# stmbluepill.net
KiCad netlist of a schematic drawn in EAGLE
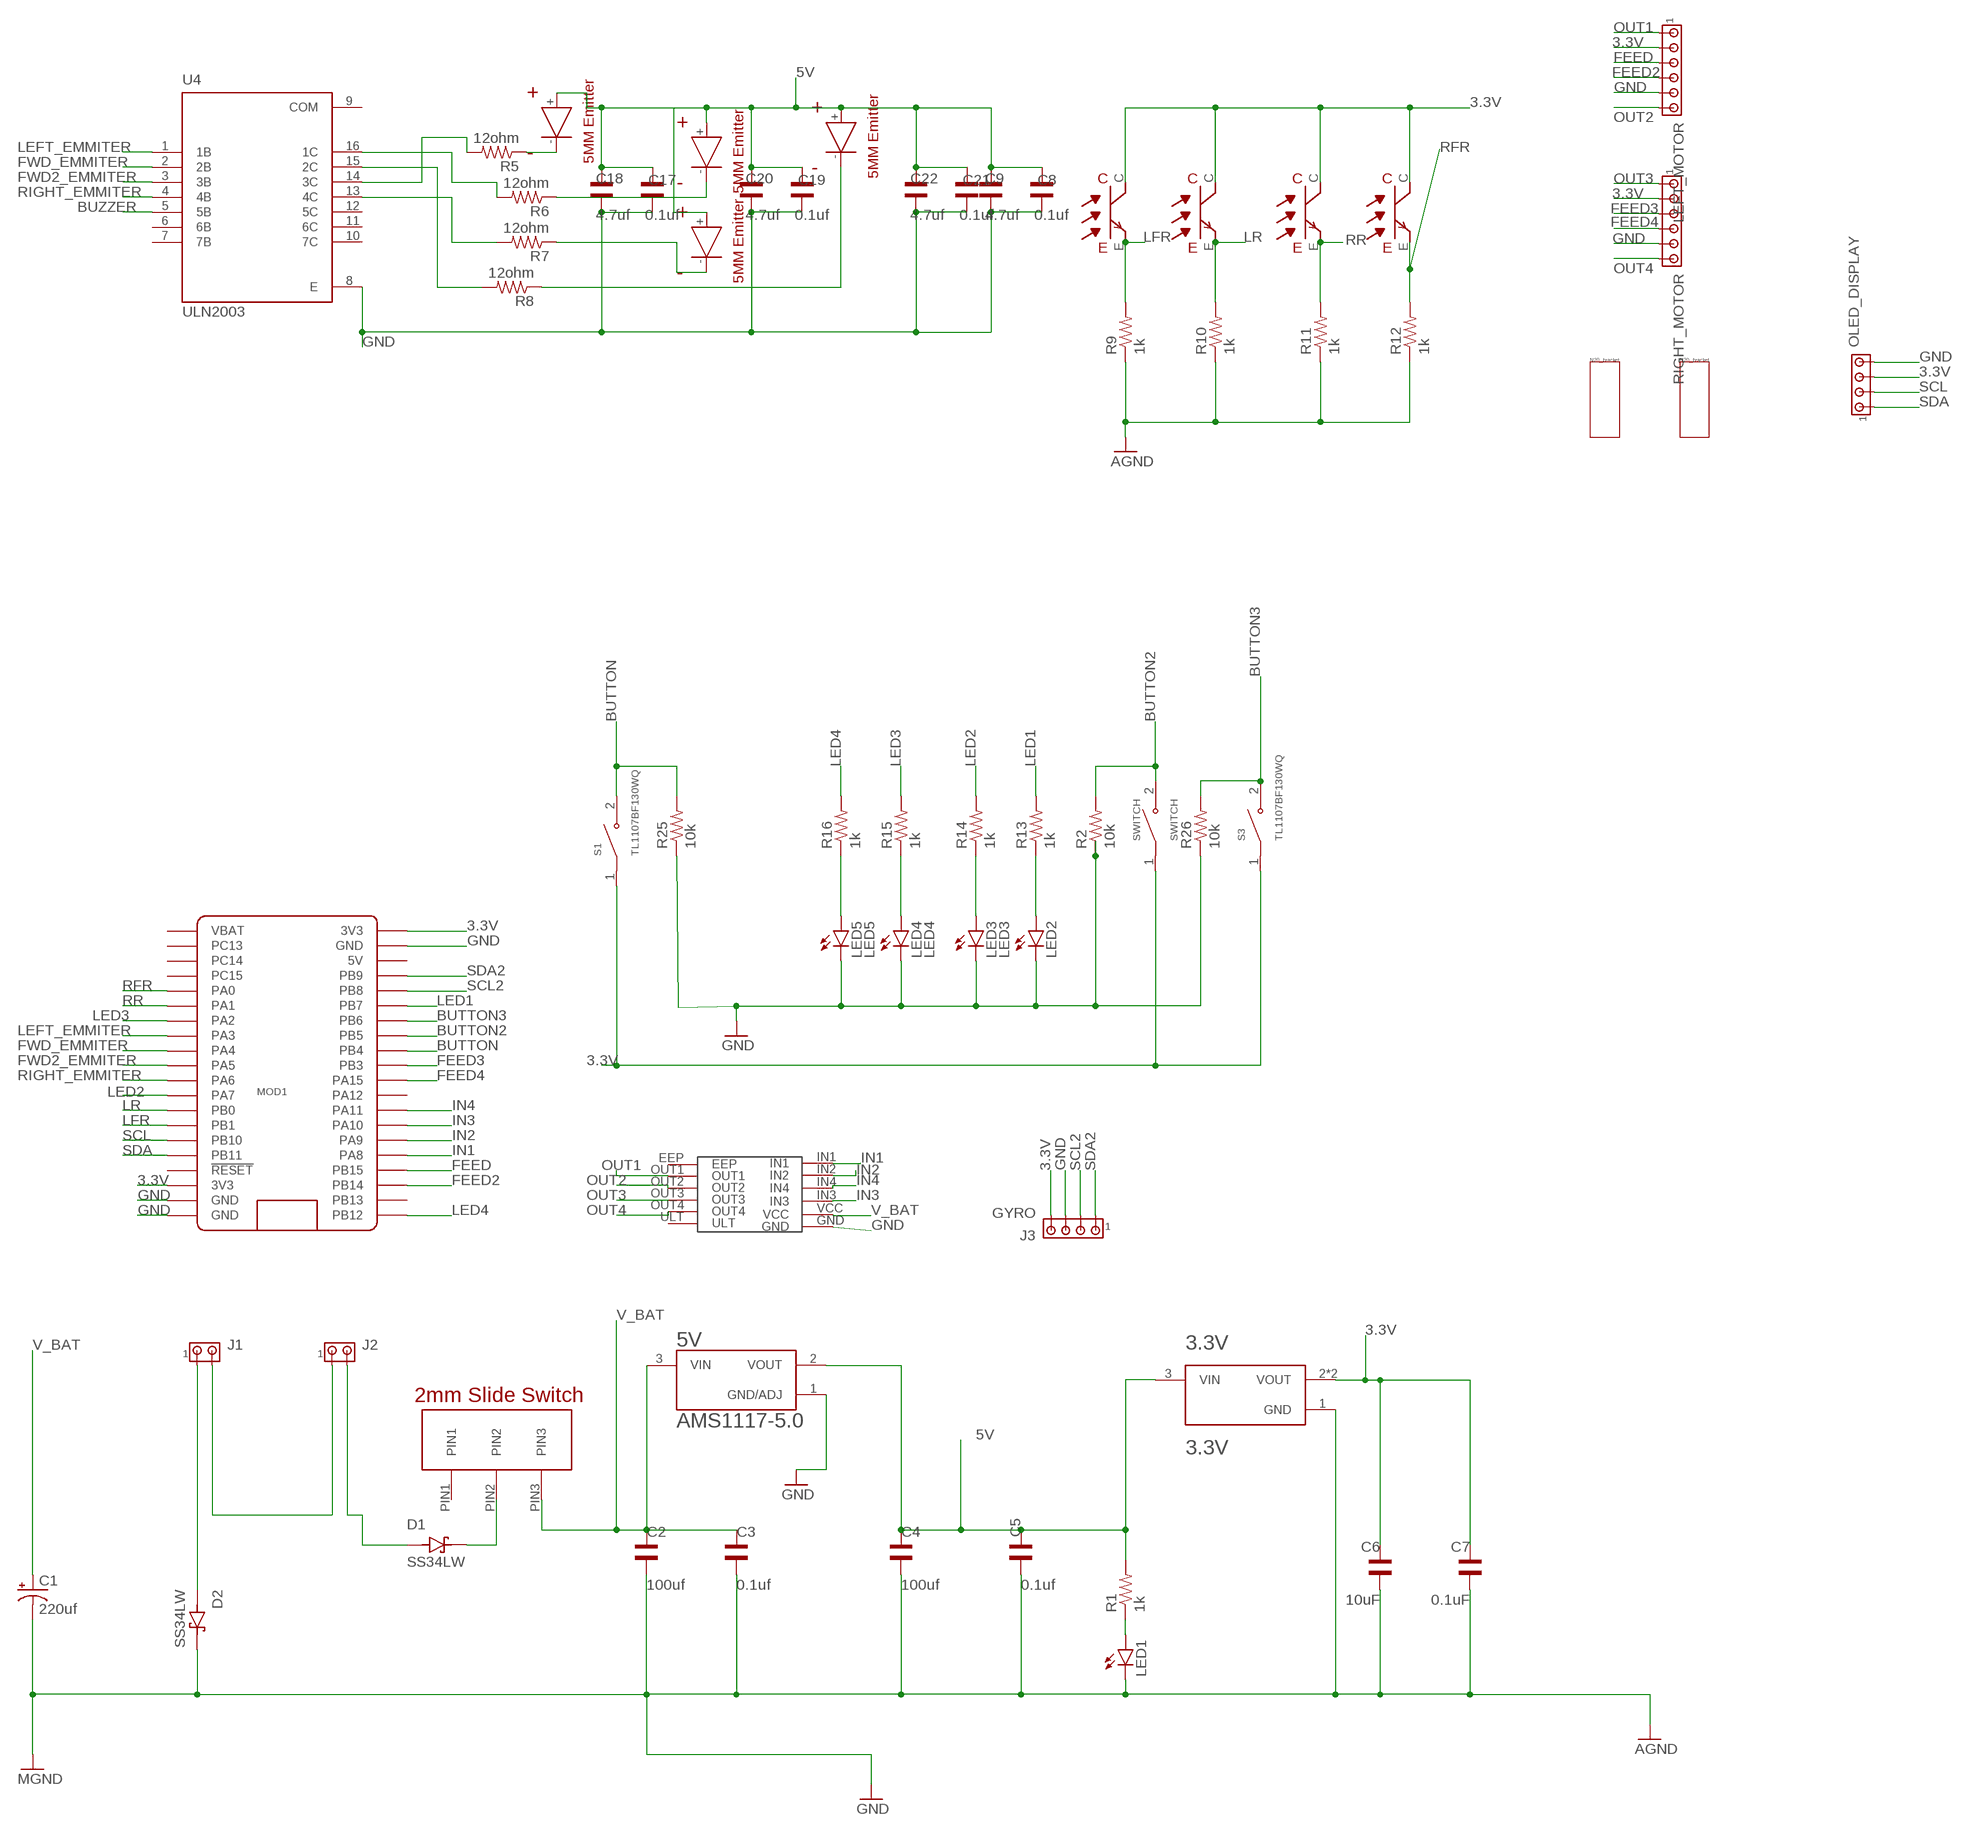
[diagram p0: schematic, sheet 1]

(export (version "E")
  (design (tool "Eeschema 10.0.6"))
  (components
    (comp (ref "3.3V")
      (value "3.3V")
      (footprint "eagle-import:SOT230P700X180-4N")
      (fields (field (name "MF") "STMicroelectronics") (field (name "MP") "LDL1117S33R"))
      (libsource (lib "eagle-import") (part "LDL1117S33R"))
    )
    (comp (ref "5V")
      (value "AMS1117-5.0")
      (footprint "eagle-import:SOT229P700X180-4N")
      (fields (field (name "MF") "Advanced Monolithic Systems"))
      (libsource (lib "eagle-import") (part "AMS1117-5.0"))
    )
    (comp (ref "C1")
      (value "220uf")
      (footprint "eagle-import:EIA3216")
      (libsource (lib "eagle-import") (part "CAP_POL1206"))
    )
    (comp (ref "C2")
      (value "100uf")
      (footprint "eagle-import:WCAP-CSGP_885012206026")
      (fields (field (name "MF") "Würth Elektronik") (field (name "MP") "885012206026"))
      (libsource (lib "eagle-import") (part "885012206026"))
    )
    (comp (ref "C3")
      (value "0.1uf")
      (footprint "eagle-import:WCAP-CSGP_885012206026")
      (fields (field (name "MF") "Würth Elektronik") (field (name "MP") "885012206026"))
      (libsource (lib "eagle-import") (part "885012206026"))
    )
    (comp (ref "C4")
      (value "100uf")
      (footprint "eagle-import:WCAP-CSGP_885012206026")
      (fields (field (name "MF") "Würth Elektronik") (field (name "MP") "885012206026"))
      (libsource (lib "eagle-import") (part "885012206026"))
    )
    (comp (ref "C5")
      (value "0.1uf")
      (footprint "eagle-import:WCAP-CSGP_885012206026")
      (fields (field (name "MF") "Würth Elektronik") (field (name "MP") "885012206026"))
      (libsource (lib "eagle-import") (part "885012206026"))
    )
    (comp (ref "C6")
      (value "10uF")
      (footprint "eagle-import:WCAP-CSGP_885012206026")
      (fields (field (name "MF") "Würth Elektronik") (field (name "MP") "885012206026"))
      (libsource (lib "eagle-import") (part "885012206026"))
    )
    (comp (ref "C7")
      (value "0.1uF")
      (footprint "eagle-import:WCAP-CSGP_885012206026")
      (fields (field (name "MF") "Würth Elektronik") (field (name "MP") "885012206026"))
      (libsource (lib "eagle-import") (part "885012206026"))
    )
    (comp (ref "C8")
      (value "0.1uf")
      (footprint "eagle-import:WCAP-CSGP_885012206026")
      (fields (field (name "MF") "Würth Elektronik") (field (name "MP") "885012206026"))
      (libsource (lib "eagle-import") (part "885012206026"))
    )
    (comp (ref "C9")
      (value "4.7uf")
      (footprint "eagle-import:WCAP-CSGP_885012206026")
      (fields (field (name "MF") "Würth Elektronik") (field (name "MP") "885012206026"))
      (libsource (lib "eagle-import") (part "885012206026"))
    )
    (comp (ref "C17")
      (value "0.1uf")
      (footprint "eagle-import:WCAP-CSGP_885012206026")
      (fields (field (name "MF") "Würth Elektronik") (field (name "MP") "885012206026"))
      (libsource (lib "eagle-import") (part "885012206026"))
    )
    (comp (ref "C18")
      (value "4.7uf")
      (footprint "eagle-import:WCAP-CSGP_885012206026")
      (fields (field (name "MF") "Würth Elektronik") (field (name "MP") "885012206026"))
      (libsource (lib "eagle-import") (part "885012206026"))
    )
    (comp (ref "C19")
      (value "0.1uf")
      (footprint "eagle-import:WCAP-CSGP_885012206026")
      (fields (field (name "MF") "Würth Elektronik") (field (name "MP") "885012206026"))
      (libsource (lib "eagle-import") (part "885012206026"))
    )
    (comp (ref "C20")
      (value "4.7uf")
      (footprint "eagle-import:WCAP-CSGP_885012206026")
      (fields (field (name "MF") "Würth Elektronik") (field (name "MP") "885012206026"))
      (libsource (lib "eagle-import") (part "885012206026"))
    )
    (comp (ref "C21")
      (value "0.1uf")
      (footprint "eagle-import:WCAP-CSGP_885012206026")
      (fields (field (name "MF") "Würth Elektronik") (field (name "MP") "885012206026"))
      (libsource (lib "eagle-import") (part "885012206026"))
    )
    (comp (ref "C22")
      (value "4.7uf")
      (footprint "eagle-import:WCAP-CSGP_885012206026")
      (fields (field (name "MF") "Würth Elektronik") (field (name "MP") "885012206026"))
      (libsource (lib "eagle-import") (part "885012206026"))
    )
    (comp (ref "D1")
      (value "SS34LW")
      (footprint "eagle-import:SODFL3718X102N")
      (fields (field (name "MF") "Taiwan Semiconductor"))
      (libsource (lib "eagle-import") (part "SS34LW"))
    )
    (comp (ref "D2")
      (value "SS34LW")
      (footprint "eagle-import:SODFL3718X102N")
      (fields (field (name "MF") "Taiwan Semiconductor"))
      (libsource (lib "eagle-import") (part "SS34LW"))
    )
    (comp (ref "EMMI1")
      (value "EMITTER")
      (footprint "eagle-import:EMITTER")
      (libsource (lib "eagle-import") (part "EMITTER"))
    )
    (comp (ref "J1")
      (value "MTA02-100")
      (footprint "eagle-import:10X02MTA")
      (libsource (lib "eagle-import") (part "MTA02-100"))
    )
    (comp (ref "J2")
      (value "MTA02-100")
      (footprint "eagle-import:10X02MTA")
      (libsource (lib "eagle-import") (part "MTA02-100"))
    )
    (comp (ref "J3")
      (value "GYRO")
      (footprint "eagle-import:10X04MTA")
      (libsource (lib "eagle-import") (part "MTA04-100"))
    )
    (comp (ref "LED1")
      (value "LEDCHIPLED_0805")
      (footprint "eagle-import:CHIPLED_0805")
      (libsource (lib "eagle-import") (part "LEDCHIPLED_0805"))
    )
    (comp (ref "LED2")
      (value "LEDCHIPLED_0805")
      (footprint "eagle-import:CHIPLED_0805")
      (libsource (lib "eagle-import") (part "LEDCHIPLED_0805"))
    )
    (comp (ref "LED3")
      (value "LED3")
      (footprint "eagle-import:CHIPLED_0805")
      (libsource (lib "eagle-import") (part "LEDCHIPLED_0805"))
    )
    (comp (ref "LED4")
      (value "LED4")
      (footprint "eagle-import:CHIPLED_0805")
      (libsource (lib "eagle-import") (part "LEDCHIPLED_0805"))
    )
    (comp (ref "LED5")
      (value "LED5")
      (footprint "eagle-import:CHIPLED_0805")
      (libsource (lib "eagle-import") (part "LEDCHIPLED_0805"))
    )
    (comp (ref "LEFT_MOTOR")
      (value "MTA06-100")
      (footprint "eagle-import:10X06MTA")
      (libsource (lib "eagle-import") (part "MTA06-100"))
    )
    (comp (ref "MOD1")
      (value "BLUE_PILLADVANCED")
      (footprint "eagle-import:BLUE_PILL_ADV")
      (libsource (lib "eagle-import") (part "BLUE_PILLADVANCED"))
    )
    (comp (ref "OLED_DISPLAY")
      (value "MTA04-100")
      (footprint "eagle-import:10X04MTA")
      (libsource (lib "eagle-import") (part "MTA04-100"))
    )
    (comp (ref "R1")
      (value "1k")
      (footprint "eagle-import:0603-RES")
      (libsource (lib "eagle-import") (part "RESISTOR0603-RES"))
    )
    (comp (ref "R2")
      (value "10k")
      (footprint "eagle-import:0603-RES")
      (libsource (lib "eagle-import") (part "RESISTOR0603-RES"))
    )
    (comp (ref "R5")
      (value "12ohm")
      (footprint "eagle-import:0603-RES")
      (libsource (lib "eagle-import") (part "RESISTOR0603-RES"))
    )
    (comp (ref "R6")
      (value "12ohm")
      (footprint "eagle-import:0603-RES")
      (libsource (lib "eagle-import") (part "RESISTOR0603-RES"))
    )
    (comp (ref "R7")
      (value "12ohm")
      (footprint "eagle-import:0603-RES")
      (libsource (lib "eagle-import") (part "RESISTOR0603-RES"))
    )
    (comp (ref "R8")
      (value "12ohm")
      (footprint "eagle-import:0603-RES")
      (libsource (lib "eagle-import") (part "RESISTOR0603-RES"))
    )
    (comp (ref "R9")
      (value "1k")
      (footprint "eagle-import:0603-RES")
      (libsource (lib "eagle-import") (part "RESISTOR0603-RES"))
    )
    (comp (ref "R10")
      (value "1k")
      (footprint "eagle-import:0603-RES")
      (libsource (lib "eagle-import") (part "RESISTOR0603-RES"))
    )
    (comp (ref "R11")
      (value "1k")
      (footprint "eagle-import:0603-RES")
      (libsource (lib "eagle-import") (part "RESISTOR0603-RES"))
    )
    (comp (ref "R12")
      (value "1k")
      (footprint "eagle-import:0603-RES")
      (libsource (lib "eagle-import") (part "RESISTOR0603-RES"))
    )
    (comp (ref "R13")
      (value "1k")
      (footprint "eagle-import:0603-RES")
      (libsource (lib "eagle-import") (part "RESISTOR0603-RES"))
    )
    (comp (ref "R14")
      (value "1k")
      (footprint "eagle-import:0603-RES")
      (libsource (lib "eagle-import") (part "RESISTOR0603-RES"))
    )
    (comp (ref "R15")
      (value "1k")
      (footprint "eagle-import:0603-RES")
      (libsource (lib "eagle-import") (part "RESISTOR0603-RES"))
    )
    (comp (ref "R16")
      (value "1k")
      (footprint "eagle-import:0603-RES")
      (libsource (lib "eagle-import") (part "RESISTOR0603-RES"))
    )
    (comp (ref "R25")
      (value "10k")
      (footprint "eagle-import:0603-RES")
      (libsource (lib "eagle-import") (part "RESISTOR0603-RES"))
    )
    (comp (ref "R26")
      (value "10k")
      (footprint "eagle-import:0603-RES")
      (libsource (lib "eagle-import") (part "RESISTOR0603-RES"))
    )
    (comp (ref "RIGHT_MOTOR")
      (value "MTA06-100")
      (footprint "eagle-import:10X06MTA")
      (libsource (lib "eagle-import") (part "MTA06-100"))
    )
    (comp (ref "S1")
      (value "TL1107BF130WQ")
      (footprint "eagle-import:SW_TL1107BF130WQ")
      (fields (field (name "MF") "E-Switch"))
      (libsource (lib "eagle-import") (part "TL1107BF130WQ"))
    )
    (comp (ref "S3")
      (value "TL1107BF130WQ")
      (footprint "eagle-import:SW_TL1107BF130WQ")
      (fields (field (name "MF") "E-Switch"))
      (libsource (lib "eagle-import") (part "TL1107BF130WQ"))
    )
    (comp (ref "SWITCH")
      (value "SWITCH")
      (footprint "eagle-import:SW_TL1107BF130WQ")
      (fields (field (name "MF") "E-Switch") (field (name "MP") "TL1107BF130WQ"))
      (libsource (lib "eagle-import") (part "TL1107BF130WQ"))
    )
    (comp (ref "U$1")
      (value "N20_BRACKET")
      (footprint "eagle-import:BRACKER")
      (libsource (lib "eagle-import") (part "N20_BRACKET"))
    )
    (comp (ref "U$4")
      (value "N20_BRACKET")
      (footprint "eagle-import:BRACKER")
      (libsource (lib "eagle-import") (part "N20_BRACKET"))
    )
    (comp (ref "U$8")
      (value "2MMS_SLIDE_SWITCH")
      (footprint "eagle-import:2MMS_SLIDE_SWITCH")
      (libsource (lib "eagle-import") (part "2MMS_SLIDE_SWITCH"))
    )
    (comp (ref "U$11")
      (value "DRV8833")
      (footprint "eagle-import:DRV8833")
      (libsource (lib "eagle-import") (part "DRV8833"))
    )
    (comp (ref "U$12")
      (value "RECEIVER")
      (footprint "eagle-import:RECEIVER")
      (libsource (lib "eagle-import") (part "RECEIVER"))
    )
    (comp (ref "U$13")
      (value "EMITTER")
      (footprint "eagle-import:EMITTER")
      (libsource (lib "eagle-import") (part "EMITTER"))
    )
    (comp (ref "U$14")
      (value "EMITTER")
      (footprint "eagle-import:EMITTER")
      (libsource (lib "eagle-import") (part "EMITTER"))
    )
    (comp (ref "U$15")
      (value "EMITTER")
      (footprint "eagle-import:EMITTER")
      (libsource (lib "eagle-import") (part "EMITTER"))
    )
    (comp (ref "U$16")
      (value "RECEIVER")
      (footprint "eagle-import:RECEIVER")
      (libsource (lib "eagle-import") (part "RECEIVER"))
    )
    (comp (ref "U$17")
      (value "RECEIVER")
      (footprint "eagle-import:RECEIVER")
      (libsource (lib "eagle-import") (part "RECEIVER"))
    )
    (comp (ref "U$18")
      (value "RECEIVER")
      (footprint "eagle-import:RECEIVER")
      (libsource (lib "eagle-import") (part "RECEIVER"))
    )
    (comp (ref "U4")
      (value "ULN2003")
      (footprint "eagle-import:SOP65P640X120-16N")
      (fields (field (name "MF") "Texas Instruments") (field (name "MP") "ULN2003APWR"))
      (libsource (lib "eagle-import") (part "ULN2003APWR"))
    )
  )
  (nets
    (net (code "1") (name "/3.3V") (class "Default")
      (node (ref "3.3V") (pin "2") (pinfunction "VOUT_2") (pintype "output"))
      (node (ref "3.3V") (pin "4") (pinfunction "VOUT_4") (pintype "output"))
      (node (ref "C6") (pin "2") (pinfunction "2_2") (pintype "passive"))
      (node (ref "C7") (pin "2") (pinfunction "2_2") (pintype "passive"))
      (node (ref "J3") (pin "4") (pinfunction "4_4") (pintype "passive"))
      (node (ref "LEFT_MOTOR") (pin "2") (pinfunction "2_2") (pintype "passive"))
      (node (ref "MOD1") (pin "P$20") (pinfunction "3V3_P$20") (pintype "bidirectional"))
      (node (ref "MOD1") (pin "P$23") (pinfunction "3V3_P$23") (pintype "bidirectional"))
      (node (ref "OLED_DISPLAY") (pin "3") (pinfunction "3_3") (pintype "passive"))
      (node (ref "RIGHT_MOTOR") (pin "2") (pinfunction "2_2") (pintype "passive"))
      (node (ref "S1") (pin "1") (pinfunction "1_1") (pintype "passive"))
      (node (ref "S3") (pin "1") (pinfunction "1_1") (pintype "passive"))
      (node (ref "SWITCH") (pin "1") (pinfunction "1_1") (pintype "passive"))
      (node (ref "U$12") (pin "C") (pinfunction "C_C") (pintype "bidirectional"))
      (node (ref "U$16") (pin "C") (pinfunction "C_C") (pintype "bidirectional"))
      (node (ref "U$17") (pin "C") (pinfunction "C_C") (pintype "bidirectional"))
      (node (ref "U$18") (pin "C") (pinfunction "C_C") (pintype "bidirectional"))
    )
    (net (code "2") (name "/5V") (class "Default")
      (node (ref "3.3V") (pin "3") (pinfunction "VIN_3") (pintype "input"))
      (node (ref "5V") (pin "2") (pinfunction "VOUT_2") (pintype "output"))
      (node (ref "C17") (pin "2") (pinfunction "2_2") (pintype "passive"))
      (node (ref "C18") (pin "2") (pinfunction "2_2") (pintype "passive"))
      (node (ref "C19") (pin "2") (pinfunction "2_2") (pintype "passive"))
      (node (ref "C20") (pin "2") (pinfunction "2_2") (pintype "passive"))
      (node (ref "C21") (pin "2") (pinfunction "2_2") (pintype "passive"))
      (node (ref "C22") (pin "2") (pinfunction "2_2") (pintype "passive"))
      (node (ref "C4") (pin "2") (pinfunction "2_2") (pintype "passive"))
      (node (ref "C5") (pin "2") (pinfunction "2_2") (pintype "passive"))
      (node (ref "C8") (pin "2") (pinfunction "2_2") (pintype "passive"))
      (node (ref "C9") (pin "2") (pinfunction "2_2") (pintype "passive"))
      (node (ref "EMMI1") (pin "+") (pinfunction "+_+") (pintype "bidirectional"))
      (node (ref "R1") (pin "2") (pinfunction "2_2") (pintype "passive"))
      (node (ref "U$13") (pin "+") (pinfunction "+_+") (pintype "bidirectional"))
      (node (ref "U$14") (pin "+") (pinfunction "+_+") (pintype "bidirectional"))
      (node (ref "U$15") (pin "+") (pinfunction "+_+") (pintype "bidirectional"))
    )
    (net (code "3") (name "/BUTTON") (class "Default")
      (node (ref "MOD1") (pin "P$12") (pinfunction "PB4_P$12") (pintype "bidirectional"))
      (node (ref "R25") (pin "2") (pinfunction "2_2") (pintype "passive"))
      (node (ref "S1") (pin "2") (pinfunction "2_2") (pintype "passive"))
    )
    (net (code "4") (name "/BUTTON2") (class "Default")
      (node (ref "MOD1") (pin "P$13") (pinfunction "PB5_P$13") (pintype "bidirectional"))
      (node (ref "R2") (pin "2") (pinfunction "2_2") (pintype "passive"))
      (node (ref "SWITCH") (pin "2") (pinfunction "2_2") (pintype "passive"))
    )
    (net (code "5") (name "/BUTTON3") (class "Default")
      (node (ref "MOD1") (pin "P$14") (pinfunction "PB6_P$14") (pintype "bidirectional"))
      (node (ref "R26") (pin "2") (pinfunction "2_2") (pintype "passive"))
      (node (ref "S3") (pin "2") (pinfunction "2_2") (pintype "passive"))
    )
    (net (code "6") (name "/BUZZER") (class "Default")
      (node (ref "U4") (pin "5") (pinfunction "5B_5") (pintype "input"))
    )
    (net (code "7") (name "/COM") (class "Default")
      (node (ref "U4") (pin "9") (pinfunction "COM_9") (pintype "power_in"))
    )
    (net (code "8") (name "/FEED") (class "Default")
      (node (ref "LEFT_MOTOR") (pin "3") (pinfunction "3_3") (pintype "passive"))
      (node (ref "MOD1") (pin "P$4") (pinfunction "PB15_P$4") (pintype "bidirectional"))
    )
    (net (code "9") (name "/FEED2") (class "Default")
      (node (ref "LEFT_MOTOR") (pin "4") (pinfunction "4_4") (pintype "passive"))
      (node (ref "MOD1") (pin "P$3") (pinfunction "PB14_P$3") (pintype "bidirectional"))
    )
    (net (code "10") (name "/FEED3") (class "Default")
      (node (ref "MOD1") (pin "P$11") (pinfunction "PB3_P$11") (pintype "bidirectional"))
      (node (ref "RIGHT_MOTOR") (pin "3") (pinfunction "3_3") (pintype "passive"))
    )
    (net (code "11") (name "/FEED4") (class "Default")
      (node (ref "MOD1") (pin "P$10") (pinfunction "PA15_P$10") (pintype "bidirectional"))
      (node (ref "RIGHT_MOTOR") (pin "4") (pinfunction "4_4") (pintype "passive"))
    )
    (net (code "12") (name "/FWD2_EMMITER") (class "Default")
      (node (ref "MOD1") (pin "P$31") (pinfunction "PA5_P$31") (pintype "bidirectional"))
      (node (ref "U4") (pin "3") (pinfunction "3B_3") (pintype "input"))
    )
    (net (code "13") (name "/FWD_EMMITER") (class "Default")
      (node (ref "MOD1") (pin "P$32") (pinfunction "PA4_P$32") (pintype "bidirectional"))
      (node (ref "U4") (pin "2") (pinfunction "2B_2") (pintype "input"))
    )
    (net (code "14") (name "/IN1") (class "Default")
      (node (ref "MOD1") (pin "P$5") (pinfunction "PA8_P$5") (pintype "bidirectional"))
      (node (ref "U$11") (pin "IN1") (pinfunction "IN1_IN1") (pintype "bidirectional"))
    )
    (net (code "15") (name "/IN2") (class "Default")
      (node (ref "MOD1") (pin "P$6") (pinfunction "PA9_P$6") (pintype "bidirectional"))
      (node (ref "U$11") (pin "IN2") (pinfunction "IN2_IN2") (pintype "bidirectional"))
    )
    (net (code "16") (name "/IN3") (class "Default")
      (node (ref "MOD1") (pin "P$7") (pinfunction "PA10_P$7") (pintype "bidirectional"))
      (node (ref "U$11") (pin "IN3") (pinfunction "IN3_IN3") (pintype "bidirectional"))
    )
    (net (code "17") (name "/IN4") (class "Default")
      (node (ref "MOD1") (pin "P$8") (pinfunction "PA11_P$8") (pintype "bidirectional"))
      (node (ref "U$11") (pin "IN4") (pinfunction "IN4_IN4") (pintype "bidirectional"))
    )
    (net (code "18") (name "/LED1") (class "Default")
      (node (ref "MOD1") (pin "P$15") (pinfunction "PB7_P$15") (pintype "bidirectional"))
      (node (ref "R13") (pin "2") (pinfunction "2_2") (pintype "passive"))
    )
    (net (code "19") (name "/LED2") (class "Default")
      (node (ref "MOD1") (pin "P$29") (pinfunction "PA7_P$29") (pintype "bidirectional"))
      (node (ref "R14") (pin "2") (pinfunction "2_2") (pintype "passive"))
    )
    (net (code "20") (name "/LED3") (class "Default")
      (node (ref "MOD1") (pin "P$34") (pinfunction "PA2_P$34") (pintype "bidirectional"))
      (node (ref "R15") (pin "2") (pinfunction "2_2") (pintype "passive"))
    )
    (net (code "21") (name "/LED4") (class "Default")
      (node (ref "MOD1") (pin "P$1") (pinfunction "PB12_P$1") (pintype "bidirectional"))
      (node (ref "R16") (pin "2") (pinfunction "2_2") (pintype "passive"))
    )
    (net (code "22") (name "/LEFT_EMMITER") (class "Default")
      (node (ref "MOD1") (pin "P$33") (pinfunction "PA3_P$33") (pintype "bidirectional"))
      (node (ref "U4") (pin "1") (pinfunction "1B_1") (pintype "input"))
    )
    (net (code "23") (name "/LFR") (class "Default")
      (node (ref "MOD1") (pin "P$27") (pinfunction "PB1_P$27") (pintype "bidirectional"))
      (node (ref "R9") (pin "2") (pinfunction "2_2") (pintype "passive"))
      (node (ref "U$18") (pin "E") (pinfunction "E_E") (pintype "bidirectional"))
    )
    (net (code "24") (name "/LR") (class "Default")
      (node (ref "MOD1") (pin "P$28") (pinfunction "PB0_P$28") (pintype "bidirectional"))
      (node (ref "R10") (pin "2") (pinfunction "2_2") (pintype "passive"))
      (node (ref "U$17") (pin "E") (pinfunction "E_E") (pintype "bidirectional"))
    )
    (net (code "25") (name "/OUT1") (class "Default")
      (node (ref "LEFT_MOTOR") (pin "1") (pinfunction "1_1") (pintype "passive"))
      (node (ref "U$11") (pin "OUT1") (pinfunction "OUT1_OUT1") (pintype "bidirectional"))
    )
    (net (code "26") (name "/OUT2") (class "Default")
      (node (ref "LEFT_MOTOR") (pin "6") (pinfunction "6_6") (pintype "passive"))
      (node (ref "U$11") (pin "OUT2") (pinfunction "OUT2_OUT2") (pintype "bidirectional"))
    )
    (net (code "27") (name "/OUT3") (class "Default")
      (node (ref "RIGHT_MOTOR") (pin "1") (pinfunction "1_1") (pintype "passive"))
      (node (ref "U$11") (pin "OUT3") (pinfunction "OUT3_OUT3") (pintype "bidirectional"))
    )
    (net (code "28") (name "/OUT4") (class "Default")
      (node (ref "RIGHT_MOTOR") (pin "6") (pinfunction "6_6") (pintype "passive"))
      (node (ref "U$11") (pin "OUT4") (pinfunction "OUT4_OUT4") (pintype "bidirectional"))
    )
    (net (code "29") (name "/RFR") (class "Default")
      (node (ref "MOD1") (pin "P$36") (pinfunction "PA0_P$36") (pintype "bidirectional"))
      (node (ref "R12") (pin "2") (pinfunction "2_2") (pintype "passive"))
      (node (ref "U$12") (pin "E") (pinfunction "E_E") (pintype "bidirectional"))
    )
    (net (code "30") (name "/RIGHT_EMMITER") (class "Default")
      (node (ref "MOD1") (pin "P$30") (pinfunction "PA6_P$30") (pintype "bidirectional"))
      (node (ref "U4") (pin "4") (pinfunction "4B_4") (pintype "input"))
    )
    (net (code "31") (name "/RR") (class "Default")
      (node (ref "MOD1") (pin "P$35") (pinfunction "PA1_P$35") (pintype "bidirectional"))
      (node (ref "R11") (pin "2") (pinfunction "2_2") (pintype "passive"))
      (node (ref "U$16") (pin "E") (pinfunction "E_E") (pintype "bidirectional"))
    )
    (net (code "32") (name "/SCL") (class "Default")
      (node (ref "MOD1") (pin "P$26") (pinfunction "PB10_P$26") (pintype "bidirectional"))
      (node (ref "OLED_DISPLAY") (pin "2") (pinfunction "2_2") (pintype "passive"))
    )
    (net (code "33") (name "/SCL2") (class "Default")
      (node (ref "J3") (pin "2") (pinfunction "2_2") (pintype "passive"))
      (node (ref "MOD1") (pin "P$16") (pinfunction "PB8_P$16") (pintype "bidirectional"))
    )
    (net (code "34") (name "/SDA") (class "Default")
      (node (ref "MOD1") (pin "P$25") (pinfunction "PB11_P$25") (pintype "bidirectional"))
      (node (ref "OLED_DISPLAY") (pin "1") (pinfunction "1_1") (pintype "passive"))
    )
    (net (code "35") (name "/SDA2") (class "Default")
      (node (ref "J3") (pin "1") (pinfunction "1_1") (pintype "passive"))
      (node (ref "MOD1") (pin "P$17") (pinfunction "PB9_P$17") (pintype "bidirectional"))
    )
    (net (code "36") (name "/V_BAT") (class "Default")
      (node (ref "5V") (pin "3") (pinfunction "VIN_3") (pintype "input"))
      (node (ref "C1") (pin "A") (pinfunction "+_A") (pintype "passive"))
      (node (ref "C2") (pin "2") (pinfunction "2_2") (pintype "passive"))
      (node (ref "C3") (pin "2") (pinfunction "2_2") (pintype "passive"))
      (node (ref "U$11") (pin "VCC") (pinfunction "VCC_VCC") (pintype "bidirectional"))
      (node (ref "U$8") (pin "PIN3") (pinfunction "PIN3_PIN3") (pintype "bidirectional"))
    )
    (net (code "37") (name "AGND") (class "Default")
      (node (ref "3.3V") (pin "1") (pinfunction "GND_1") (pintype "power_in"))
      (node (ref "5V") (pin "1") (pinfunction "GND/ADJ_1") (pintype "power_in"))
      (node (ref "C1") (pin "C") (pinfunction "-_C") (pintype "passive"))
      (node (ref "C17") (pin "1") (pinfunction "1_1") (pintype "passive"))
      (node (ref "C18") (pin "1") (pinfunction "1_1") (pintype "passive"))
      (node (ref "C19") (pin "1") (pinfunction "1_1") (pintype "passive"))
      (node (ref "C2") (pin "1") (pinfunction "1_1") (pintype "passive"))
      (node (ref "C20") (pin "1") (pinfunction "1_1") (pintype "passive"))
      (node (ref "C21") (pin "1") (pinfunction "1_1") (pintype "passive"))
      (node (ref "C22") (pin "1") (pinfunction "1_1") (pintype "passive"))
      (node (ref "C3") (pin "1") (pinfunction "1_1") (pintype "passive"))
      (node (ref "C4") (pin "1") (pinfunction "1_1") (pintype "passive"))
      (node (ref "C5") (pin "1") (pinfunction "1_1") (pintype "passive"))
      (node (ref "C6") (pin "1") (pinfunction "1_1") (pintype "passive"))
      (node (ref "C7") (pin "1") (pinfunction "1_1") (pintype "passive"))
      (node (ref "C8") (pin "1") (pinfunction "1_1") (pintype "passive"))
      (node (ref "C9") (pin "1") (pinfunction "1_1") (pintype "passive"))
      (node (ref "D2") (pin "C") (pinfunction "K_C") (pintype "passive"))
      (node (ref "J3") (pin "3") (pinfunction "3_3") (pintype "passive"))
      (node (ref "LED1") (pin "C") (pinfunction "C_C") (pintype "passive"))
      (node (ref "LED2") (pin "C") (pinfunction "C_C") (pintype "passive"))
      (node (ref "LED3") (pin "C") (pinfunction "C_C") (pintype "passive"))
      (node (ref "LED4") (pin "C") (pinfunction "C_C") (pintype "passive"))
      (node (ref "LED5") (pin "C") (pinfunction "C_C") (pintype "passive"))
      (node (ref "LEFT_MOTOR") (pin "5") (pinfunction "5_5") (pintype "passive"))
      (node (ref "MOD1") (pin "P$19") (pinfunction "GND_P$19") (pintype "passive"))
      (node (ref "MOD1") (pin "P$21") (pinfunction "GND_P$21") (pintype "passive"))
      (node (ref "MOD1") (pin "P$22") (pinfunction "GND_P$22") (pintype "passive"))
      (node (ref "OLED_DISPLAY") (pin "4") (pinfunction "4_4") (pintype "passive"))
      (node (ref "R10") (pin "1") (pinfunction "1_1") (pintype "passive"))
      (node (ref "R11") (pin "1") (pinfunction "1_1") (pintype "passive"))
      (node (ref "R12") (pin "1") (pinfunction "1_1") (pintype "passive"))
      (node (ref "R2") (pin "1") (pinfunction "1_1") (pintype "passive"))
      (node (ref "R25") (pin "1") (pinfunction "1_1") (pintype "passive"))
      (node (ref "R26") (pin "1") (pinfunction "1_1") (pintype "passive"))
      (node (ref "R9") (pin "1") (pinfunction "1_1") (pintype "passive"))
      (node (ref "RIGHT_MOTOR") (pin "5") (pinfunction "5_5") (pintype "passive"))
      (node (ref "U$11") (pin "GND") (pinfunction "GND_GND") (pintype "bidirectional"))
      (node (ref "U4") (pin "8") (pinfunction "E_8") (pintype "power_in"))
    )
    (net (code "38") (name "Net-(D1-K)") (class "Default")
      (node (ref "D1") (pin "C") (pinfunction "K_C") (pintype "passive"))
      (node (ref "U$8") (pin "PIN2") (pinfunction "PIN2_PIN2") (pintype "bidirectional"))
    )
    (net (code "39") (name "Net-(D1-PadA)") (class "Default")
      (node (ref "D1") (pin "A") (pinfunction "A_A") (pintype "passive"))
      (node (ref "J2") (pin "2") (pinfunction "2_2") (pintype "passive"))
    )
    (net (code "40") (name "Net-(D2-PadA)") (class "Default")
      (node (ref "D2") (pin "A") (pinfunction "A_A") (pintype "passive"))
      (node (ref "J1") (pin "1") (pinfunction "1_1") (pintype "passive"))
    )
    (net (code "41") (name "Net-(EMMI1-Pad-)") (class "Default")
      (node (ref "EMMI1") (pin "-") (pinfunction "-_-") (pintype "bidirectional"))
      (node (ref "R5") (pin "1") (pinfunction "1_1") (pintype "passive"))
    )
    (net (code "42") (name "Net-(J1-Pad2)") (class "Default")
      (node (ref "J1") (pin "2") (pinfunction "2_2") (pintype "passive"))
      (node (ref "J2") (pin "1") (pinfunction "1_1") (pintype "passive"))
    )
    (net (code "43") (name "Net-(LED1-PadA)") (class "Default")
      (node (ref "LED1") (pin "A") (pinfunction "A_A") (pintype "passive"))
      (node (ref "R1") (pin "1") (pinfunction "1_1") (pintype "passive"))
    )
    (net (code "44") (name "Net-(LED2-PadA)") (class "Default")
      (node (ref "LED2") (pin "A") (pinfunction "A_A") (pintype "passive"))
      (node (ref "R13") (pin "1") (pinfunction "1_1") (pintype "passive"))
    )
    (net (code "45") (name "Net-(LED3-PadA)") (class "Default")
      (node (ref "LED3") (pin "A") (pinfunction "A_A") (pintype "passive"))
      (node (ref "R14") (pin "1") (pinfunction "1_1") (pintype "passive"))
    )
    (net (code "46") (name "Net-(LED4-PadA)") (class "Default")
      (node (ref "LED4") (pin "A") (pinfunction "A_A") (pintype "passive"))
      (node (ref "R15") (pin "1") (pinfunction "1_1") (pintype "passive"))
    )
    (net (code "47") (name "Net-(LED5-PadA)") (class "Default")
      (node (ref "LED5") (pin "A") (pinfunction "A_A") (pintype "passive"))
      (node (ref "R16") (pin "1") (pinfunction "1_1") (pintype "passive"))
    )
    (net (code "48") (name "Net-(R6-Pad1)") (class "Default")
      (node (ref "R6") (pin "1") (pinfunction "1_1") (pintype "passive"))
      (node (ref "U$13") (pin "-") (pinfunction "-_-") (pintype "bidirectional"))
    )
    (net (code "49") (name "Net-(R7-Pad1)") (class "Default")
      (node (ref "R7") (pin "1") (pinfunction "1_1") (pintype "passive"))
      (node (ref "U$14") (pin "-") (pinfunction "-_-") (pintype "bidirectional"))
    )
    (net (code "50") (name "Net-(R8-Pad1)") (class "Default")
      (node (ref "R8") (pin "1") (pinfunction "1_1") (pintype "passive"))
      (node (ref "U$15") (pin "-") (pinfunction "-_-") (pintype "bidirectional"))
    )
    (net (code "51") (name "Net-(U4-1C)") (class "Default")
      (node (ref "R6") (pin "2") (pinfunction "2_2") (pintype "passive"))
      (node (ref "U4") (pin "16") (pinfunction "1C_16") (pintype "output"))
    )
    (net (code "52") (name "Net-(U4-2C)") (class "Default")
      (node (ref "R8") (pin "2") (pinfunction "2_2") (pintype "passive"))
      (node (ref "U4") (pin "15") (pinfunction "2C_15") (pintype "output"))
    )
    (net (code "53") (name "Net-(U4-3C)") (class "Default")
      (node (ref "R5") (pin "2") (pinfunction "2_2") (pintype "passive"))
      (node (ref "U4") (pin "14") (pinfunction "3C_14") (pintype "output"))
    )
    (net (code "54") (name "Net-(U4-4C)") (class "Default")
      (node (ref "R7") (pin "2") (pinfunction "2_2") (pintype "passive"))
      (node (ref "U4") (pin "13") (pinfunction "4C_13") (pintype "output"))
    )
    (net (code "55") (name "unconnected-(MOD1-5V-PadP$18)") (class "Default")
      (node (ref "MOD1") (pin "P$18") (pinfunction "5V_P$18") (pintype "bidirectional"))
    )
    (net (code "56") (name "unconnected-(MOD1-PA12-PadP$9)") (class "Default")
      (node (ref "MOD1") (pin "P$9") (pinfunction "PA12_P$9") (pintype "bidirectional"))
    )
    (net (code "57") (name "unconnected-(MOD1-PB13-PadP$2)") (class "Default")
      (node (ref "MOD1") (pin "P$2") (pinfunction "PB13_P$2") (pintype "bidirectional"))
    )
    (net (code "58") (name "unconnected-(MOD1-PC13-PadP$39)") (class "Default")
      (node (ref "MOD1") (pin "P$39") (pinfunction "PC13_P$39") (pintype "bidirectional"))
    )
    (net (code "59") (name "unconnected-(MOD1-PC14-PadP$38)") (class "Default")
      (node (ref "MOD1") (pin "P$38") (pinfunction "PC14_P$38") (pintype "bidirectional"))
    )
    (net (code "60") (name "unconnected-(MOD1-PC15-PadP$37)") (class "Default")
      (node (ref "MOD1") (pin "P$37") (pinfunction "PC15_P$37") (pintype "bidirectional"))
    )
    (net (code "61") (name "unconnected-(MOD1-VBAT-PadP$40)") (class "Default")
      (node (ref "MOD1") (pin "P$40") (pinfunction "VBAT_P$40") (pintype "bidirectional"))
    )
    (net (code "62") (name "unconnected-(MOD1-~{RESET}-PadP$24)") (class "Default")
      (node (ref "MOD1") (pin "P$24") (pinfunction "~{RESET}_P$24") (pintype "bidirectional"))
    )
    (net (code "63") (name "unconnected-(U$8-PadPIN1)") (class "Default")
      (node (ref "U$8") (pin "PIN1") (pinfunction "PIN1_PIN1") (pintype "bidirectional"))
    )
    (net (code "64") (name "unconnected-(U$11-PadEEP)") (class "Default")
      (node (ref "U$11") (pin "EEP") (pinfunction "EEP_EEP") (pintype "bidirectional"))
    )
    (net (code "65") (name "unconnected-(U$11-PadULT)") (class "Default")
      (node (ref "U$11") (pin "ULT") (pinfunction "ULT_ULT") (pintype "bidirectional"))
    )
    (net (code "66") (name "unconnected-(U4-5C-Pad12)") (class "Default")
      (node (ref "U4") (pin "12") (pinfunction "5C_12") (pintype "output"))
    )
    (net (code "67") (name "unconnected-(U4-6B-Pad6)") (class "Default")
      (node (ref "U4") (pin "6") (pinfunction "6B_6") (pintype "input"))
    )
    (net (code "68") (name "unconnected-(U4-6C-Pad11)") (class "Default")
      (node (ref "U4") (pin "11") (pinfunction "6C_11") (pintype "output"))
    )
    (net (code "69") (name "unconnected-(U4-7B-Pad7)") (class "Default")
      (node (ref "U4") (pin "7") (pinfunction "7B_7") (pintype "input"))
    )
    (net (code "70") (name "unconnected-(U4-7C-Pad10)") (class "Default")
      (node (ref "U4") (pin "10") (pinfunction "7C_10") (pintype "output"))
    )
  )
)
